# nh-vend_v0_2.net
KiCad netlist of a schematic drawn in EAGLE
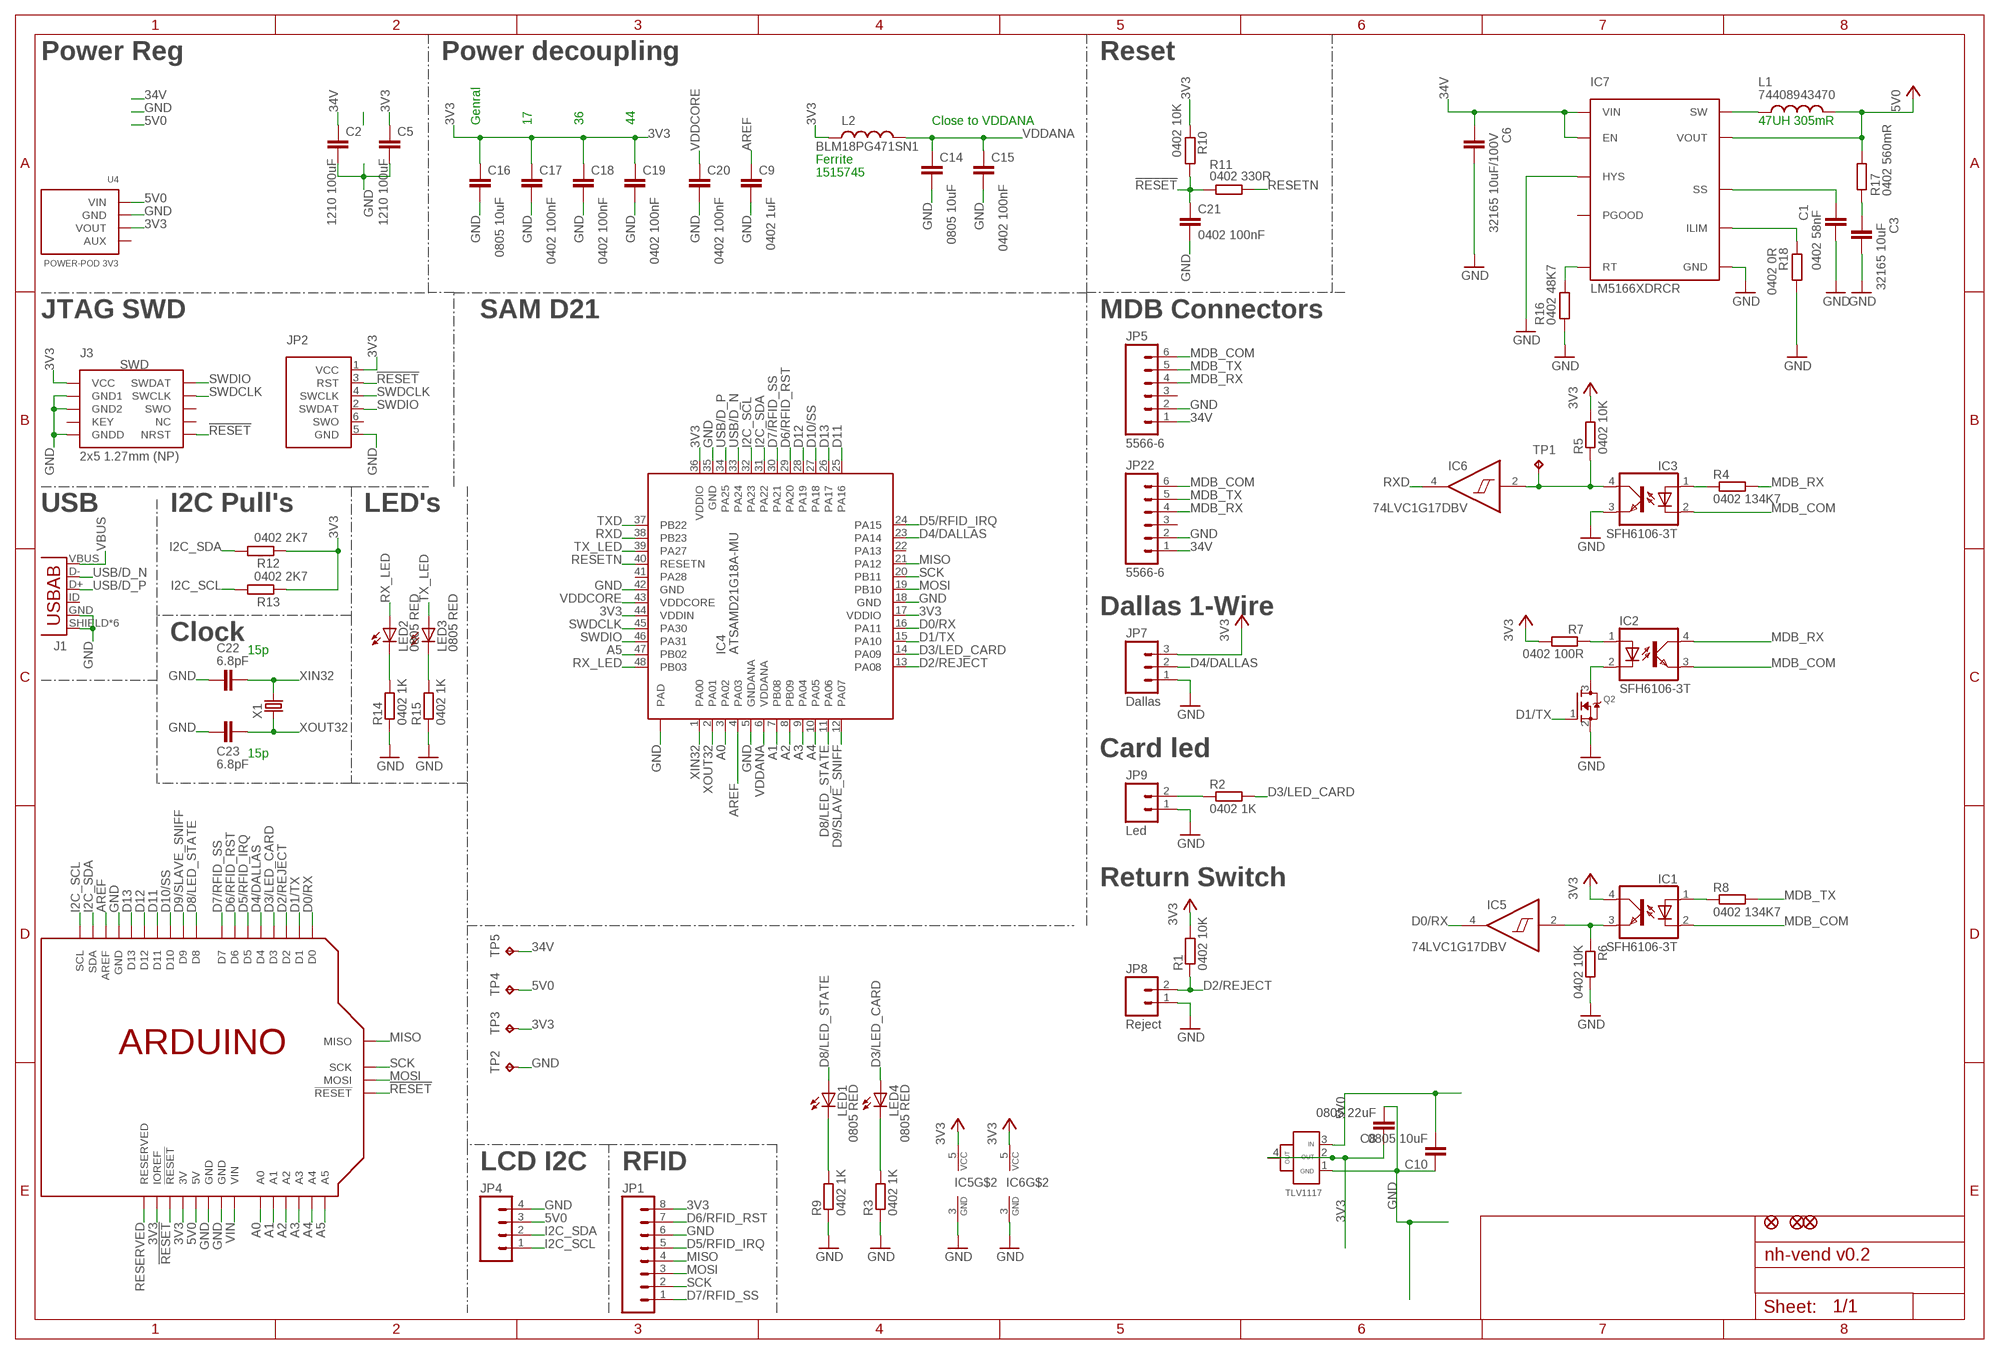
[diagram p0: schematic, sheet 1]

(export (version "E")
  (design (tool "Eeschema 10.0.6"))
  (components
    (comp (ref "C1")
      (value "0402 58nF")
      (footprint "eagle-import:C0402-SMALLER")
      (libsource (lib "eagle-import") (part "C-EUC0402-SMALLER"))
    )
    (comp (ref "C2")
      (value "1210 100uF")
      (footprint "eagle-import:C1210")
      (libsource (lib "eagle-import") (part "C-EUC1210"))
    )
    (comp (ref "C3")
      (value "32165 10uF")
      (footprint "eagle-import:C3216")
      (libsource (lib "eagle-import") (part "C-EUC3216"))
    )
    (comp (ref "C5")
      (value "1210 100uF")
      (footprint "eagle-import:C1210")
      (libsource (lib "eagle-import") (part "C-EUC1210"))
    )
    (comp (ref "C6")
      (value "32165 10uF/100V")
      (footprint "eagle-import:C3216")
      (libsource (lib "eagle-import") (part "C-EUC3216"))
    )
    (comp (ref "C8")
      (value "0805 22uF")
      (footprint "eagle-import:C0805")
      (libsource (lib "eagle-import") (part "rcl_C-EUC0805"))
    )
    (comp (ref "C9")
      (value "0402 1uF")
      (footprint "eagle-import:C0402-SMALLER")
      (libsource (lib "eagle-import") (part "C-EUC0402-SMALLER"))
    )
    (comp (ref "C10")
      (value "0805 10uF")
      (footprint "eagle-import:C0805")
      (libsource (lib "eagle-import") (part "rcl_C-EUC0805"))
    )
    (comp (ref "C14")
      (value "0805 10uF")
      (footprint "eagle-import:C0805K")
      (libsource (lib "eagle-import") (part "C-EUC0805K"))
    )
    (comp (ref "C15")
      (value "0402 100nF")
      (footprint "eagle-import:C0402-SMALLER")
      (libsource (lib "eagle-import") (part "C-EUC0402-SMALLER"))
    )
    (comp (ref "C16")
      (value "0805 10uF")
      (footprint "eagle-import:C0805K")
      (libsource (lib "eagle-import") (part "C-EUC0805K"))
    )
    (comp (ref "C17")
      (value "0402 100nF")
      (footprint "eagle-import:C0402-SMALLER")
      (libsource (lib "eagle-import") (part "C-EUC0402-SMALLER"))
    )
    (comp (ref "C18")
      (value "0402 100nF")
      (footprint "eagle-import:C0402-SMALLER")
      (libsource (lib "eagle-import") (part "C-EUC0402-SMALLER"))
    )
    (comp (ref "C19")
      (value "0402 100nF")
      (footprint "eagle-import:C0402-SMALLER")
      (libsource (lib "eagle-import") (part "C-EUC0402-SMALLER"))
    )
    (comp (ref "C20")
      (value "0402 100nF")
      (footprint "eagle-import:C0402-SMALLER")
      (libsource (lib "eagle-import") (part "C-EUC0402-SMALLER"))
    )
    (comp (ref "C21")
      (value "0402 100nF")
      (footprint "eagle-import:C0402-SMALLER")
      (libsource (lib "eagle-import") (part "C-EUC0402-SMALLER"))
    )
    (comp (ref "C22")
      (value "6.8pF")
      (footprint "eagle-import:C0402-SMALLER")
      (libsource (lib "eagle-import") (part "C-EUC0402-SMALLER"))
    )
    (comp (ref "C23")
      (value "6.8pF")
      (footprint "eagle-import:C0402-SMALLER")
      (libsource (lib "eagle-import") (part "C-EUC0402-SMALLER"))
    )
    (comp (ref "IC1")
      (value "SFH6106-3T")
      (footprint "eagle-import:SO04")
      (libsource (lib "eagle-import") (part "OPTO-DC"))
    )
    (comp (ref "IC2")
      (value "SFH6106-3T")
      (footprint "eagle-import:SO04")
      (libsource (lib "eagle-import") (part "OPTO-DC"))
    )
    (comp (ref "IC3")
      (value "SFH6106-3T")
      (footprint "eagle-import:SO04")
      (libsource (lib "eagle-import") (part "OPTO-DC"))
    )
    (comp (ref "IC4")
      (value "ATSAMD21G18A-MU")
      (footprint "eagle-import:QFN48-LWK")
      (libsource (lib "eagle-import") (part "ATSAMD21G-LWK"))
    )
    (comp (ref "IC5")
      (value "74LVC1G17DBV")
      (footprint "eagle-import:SOT23-5")
      (libsource (lib "eagle-import") (part "741G17DBVLVC"))
    )
    (comp (ref "IC6")
      (value "74LVC1G17DBV")
      (footprint "eagle-import:SOT23-5")
      (libsource (lib "eagle-import") (part "741G17DBVLVC"))
    )
    (comp (ref "IC7")
      (value "LM5166XDRCR")
      (footprint "eagle-import:VSON-10")
      (libsource (lib "eagle-import") (part "LM5166"))
    )
    (comp (ref "J1")
      (value "ZX62-AB-5PA(11)")
      (footprint "eagle-import:USB-AB-MICRO-SMD_LWK")
      (libsource (lib "eagle-import") (part "USB-AB-LWK"))
    )
    (comp (ref "J3")
      (value "2x5 1.27mm (NP)")
      (footprint "eagle-import:PINHEAD_2X05_127")
      (libsource (lib "eagle-import") (part "SWD_SHROUD-PINHEAD"))
    )
    (comp (ref "JP1")
      (value "M081X08")
      (footprint "eagle-import:1X08")
      (libsource (lib "eagle-import") (part "M081X08"))
    )
    (comp (ref "JP2")
      (value "(NP)")
      (footprint "eagle-import:TC2030-MCP-NL")
      (libsource (lib "eagle-import") (part "TC2030-SWDNL"))
    )
    (comp (ref "JP3")
      (value "FIDUCIAL1X2.5-STOP")
      (footprint "eagle-import:FIDUCIAL-1X2.5-STOP")
      (libsource (lib "eagle-import") (part "FIDUCIAL1X2.5-STOP"))
    )
    (comp (ref "JP4")
      (value "M04PTH")
      (footprint "eagle-import:1X04")
      (libsource (lib "eagle-import") (part "M04PTH"))
    )
    (comp (ref "JP5")
      (value "5566-6")
      (footprint "eagle-import:5566-6")
      (fields (field (name "MF") "Molex"))
      (libsource (lib "eagle-import") (part "M06-5566"))
    )
    (comp (ref "JP6")
      (value "FIDUCIAL1X2.5-STOP")
      (footprint "eagle-import:FIDUCIAL-1X2.5-STOP")
      (libsource (lib "eagle-import") (part "FIDUCIAL1X2.5-STOP"))
    )
    (comp (ref "JP7")
      (value "Dallas")
      (footprint "eagle-import:SCREWTERMINAL-5MM-3")
      (libsource (lib "eagle-import") (part "M03-SCREW-5MM"))
    )
    (comp (ref "JP8")
      (value "Reject")
      (footprint "eagle-import:SCREWTERMINAL-5MM-2")
      (libsource (lib "eagle-import") (part "M025MM"))
    )
    (comp (ref "JP9")
      (value "Led")
      (footprint "eagle-import:SCREWTERMINAL-5MM-2")
      (libsource (lib "eagle-import") (part "M025MM"))
    )
    (comp (ref "JP10")
      (value "FIDUCIAL1X2.5-STOP")
      (footprint "eagle-import:FIDUCIAL-1X2.5-STOP")
      (libsource (lib "eagle-import") (part "FIDUCIAL1X2.5-STOP"))
    )
    (comp (ref "JP22")
      (value "5566-6")
      (footprint "eagle-import:5566-6")
      (fields (field (name "MF") "Molex"))
      (libsource (lib "eagle-import") (part "M06-5566"))
    )
    (comp (ref "L1")
      (value "74408943470")
      (footprint "eagle-import:WE-SPC_48XX")
      (libsource (lib "eagle-import") (part "INDUCTOR-WE-SPC"))
    )
    (comp (ref "L2")
      (value "BLM18PG471SN1")
      (footprint "eagle-import:C0603K-SMALL")
      (libsource (lib "eagle-import") (part "INDUCTOR0603K-SMALL"))
    )
    (comp (ref "LED1")
      (value "0805 RED")
      (footprint "eagle-import:LED-0805-1206")
      (libsource (lib "eagle-import") (part "LED0805-1206"))
    )
    (comp (ref "LED2")
      (value "0805 RED")
      (footprint "eagle-import:LED-0805-1206")
      (libsource (lib "eagle-import") (part "LED0805-1206"))
    )
    (comp (ref "LED3")
      (value "0805 RED")
      (footprint "eagle-import:LED-0805-1206")
      (libsource (lib "eagle-import") (part "LED0805-1206"))
    )
    (comp (ref "LED4")
      (value "0805 RED")
      (footprint "eagle-import:LED-0805-1206")
      (libsource (lib "eagle-import") (part "LED0805-1206"))
    )
    (comp (ref "Q2")
      (value "MOSFET-N-SOT23-SPARK")
      (footprint "eagle-import:SOT23-3")
      (libsource (lib "eagle-import") (part "MOSFET-N-SOT23-SPARK"))
    )
    (comp (ref "R1")
      (value "0402 10K")
      (footprint "eagle-import:R0402-SMALLER")
      (libsource (lib "eagle-import") (part "R-EU_R0402-SMALLER"))
    )
    (comp (ref "R2")
      (value "0402 1K")
      (footprint "eagle-import:R0402-SMALLER")
      (libsource (lib "eagle-import") (part "R-EU_R0402-SMALLER"))
    )
    (comp (ref "R3")
      (value "0402 1K")
      (footprint "eagle-import:R0402-SMALLER")
      (libsource (lib "eagle-import") (part "R-EU_R0402-SMALLER"))
    )
    (comp (ref "R4")
      (value "0402 134K7")
      (footprint "eagle-import:R0402-SMALLER")
      (libsource (lib "eagle-import") (part "R-EU_R0402-SMALLER"))
    )
    (comp (ref "R5")
      (value "0402 10K")
      (footprint "eagle-import:R0402-SMALLER")
      (libsource (lib "eagle-import") (part "R-EU_R0402-SMALLER"))
    )
    (comp (ref "R6")
      (value "0402 10K")
      (footprint "eagle-import:R0402-SMALLER")
      (libsource (lib "eagle-import") (part "R-EU_R0402-SMALLER"))
    )
    (comp (ref "R7")
      (value "0402 100R")
      (footprint "eagle-import:R0402-SMALLER")
      (libsource (lib "eagle-import") (part "R-EU_R0402-SMALLER"))
    )
    (comp (ref "R8")
      (value "0402 134K7")
      (footprint "eagle-import:R0402-SMALLER")
      (libsource (lib "eagle-import") (part "R-EU_R0402-SMALLER"))
    )
    (comp (ref "R9")
      (value "0402 1K")
      (footprint "eagle-import:R0402-SMALLER")
      (libsource (lib "eagle-import") (part "R-EU_R0402-SMALLER"))
    )
    (comp (ref "R10")
      (value "0402 10K")
      (footprint "eagle-import:R0402-SMALLER")
      (libsource (lib "eagle-import") (part "R-EU_R0402-SMALLER"))
    )
    (comp (ref "R11")
      (value "0402 330R")
      (footprint "eagle-import:R0402-SMALLER")
      (libsource (lib "eagle-import") (part "R-EU_R0402-SMALLER"))
    )
    (comp (ref "R12")
      (value "0402 2K7")
      (footprint "eagle-import:R0402-SMALLER")
      (libsource (lib "eagle-import") (part "R-EU_R0402-SMALLER"))
    )
    (comp (ref "R13")
      (value "0402 2K7")
      (footprint "eagle-import:R0402-SMALLER")
      (libsource (lib "eagle-import") (part "R-EU_R0402-SMALLER"))
    )
    (comp (ref "R14")
      (value "0402 1K")
      (footprint "eagle-import:R0402-SMALLER")
      (libsource (lib "eagle-import") (part "R-EU_R0402-SMALLER"))
    )
    (comp (ref "R15")
      (value "0402 1K")
      (footprint "eagle-import:R0402-SMALLER")
      (libsource (lib "eagle-import") (part "R-EU_R0402-SMALLER"))
    )
    (comp (ref "R16")
      (value "0402 48K7")
      (footprint "eagle-import:R0402-SMALLER")
      (libsource (lib "eagle-import") (part "R-EU_R0402-SMALLER"))
    )
    (comp (ref "R17")
      (value "0402 560mR")
      (footprint "eagle-import:R0402-SMALLER")
      (libsource (lib "eagle-import") (part "R-EU_R0402-SMALLER"))
    )
    (comp (ref "R18")
      (value "0402 0R")
      (footprint "eagle-import:R0402-SMALLER")
      (libsource (lib "eagle-import") (part "R-EU_R0402-SMALLER"))
    )
    (comp (ref "TP1")
      (value "TPPAD1-10-ROUND")
      (footprint "eagle-import:P1-10-ROUND-CAN")
      (libsource (lib "eagle-import") (part "TPPAD1-10-ROUND"))
    )
    (comp (ref "TP2")
      (value "TPPAD1-10-ROUND")
      (footprint "eagle-import:P1-10-ROUND-CAN")
      (libsource (lib "eagle-import") (part "TPPAD1-10-ROUND"))
    )
    (comp (ref "TP3")
      (value "TPPAD1-10-ROUND")
      (footprint "eagle-import:P1-10-ROUND-CAN")
      (libsource (lib "eagle-import") (part "TPPAD1-10-ROUND"))
    )
    (comp (ref "TP4")
      (value "TPPAD1-10-ROUND")
      (footprint "eagle-import:P1-10-ROUND-CAN")
      (libsource (lib "eagle-import") (part "TPPAD1-10-ROUND"))
    )
    (comp (ref "TP5")
      (value "TPPAD1-10-ROUND")
      (footprint "eagle-import:P1-10-ROUND-CAN")
      (libsource (lib "eagle-import") (part "TPPAD1-10-ROUND"))
    )
    (comp (ref "U1")
      (value "ARDUINOSPI-REFRENCE")
      (footprint "eagle-import:ARDUINOR3-LWKTXT-REF-SPI")
      (libsource (lib "eagle-import") (part "ARDUINOSPI-REFRENCE"))
    )
    (comp (ref "U03")
      (value "1117 3V0")
      (footprint "eagle-import:SOT223")
      (libsource (lib "eagle-import") (part "TLV1117-33CDCY"))
    )
    (comp (ref "U4")
      (value "POWER-POD 3V3")
      (footprint "eagle-import:POWER-POD-LANDING")
      (libsource (lib "eagle-import") (part "POWER-POD"))
    )
    (comp (ref "X1")
      (value "RESONATOR_EPSON_FC_145")
      (footprint "eagle-import:RESONATOR_EPSON_FC_145")
      (libsource (lib "eagle-import") (part "RESONATOR_EPSON_FC_145"))
    )
  )
  (nets
    (net (code "1") (name "/34V") (class "Default")
      (node (ref "C2") (pin "1") (pinfunction "1_1") (pintype "passive"))
      (node (ref "C6") (pin "1") (pinfunction "1_1") (pintype "passive"))
      (node (ref "IC7") (pin "2") (pinfunction "VIN_2") (pintype "bidirectional"))
      (node (ref "IC7") (pin "7") (pinfunction "EN_7") (pintype "bidirectional"))
      (node (ref "JP22") (pin "1") (pinfunction "1_1") (pintype "passive"))
      (node (ref "JP5") (pin "1") (pinfunction "1_1") (pintype "passive"))
      (node (ref "TP5") (pin "TP") (pinfunction "TP_TP") (pintype "input"))
    )
    (net (code "2") (name "/A0") (class "Default")
      (node (ref "IC4") (pin "3") (pinfunction "PA02_3") (pintype "bidirectional"))
      (node (ref "U1") (pin "A0") (pinfunction "A0_A0") (pintype "bidirectional"))
    )
    (net (code "3") (name "/A1") (class "Default")
      (node (ref "IC4") (pin "7") (pinfunction "PB08_7") (pintype "bidirectional"))
      (node (ref "U1") (pin "A1") (pinfunction "A1_A1") (pintype "bidirectional"))
    )
    (net (code "4") (name "/A2") (class "Default")
      (node (ref "IC4") (pin "8") (pinfunction "PB09_8") (pintype "bidirectional"))
      (node (ref "U1") (pin "A2") (pinfunction "A2_A2") (pintype "bidirectional"))
    )
    (net (code "5") (name "/A3") (class "Default")
      (node (ref "IC4") (pin "9") (pinfunction "PA04_9") (pintype "bidirectional"))
      (node (ref "U1") (pin "A3") (pinfunction "A3_A3") (pintype "bidirectional"))
    )
    (net (code "6") (name "/A4") (class "Default")
      (node (ref "IC4") (pin "10") (pinfunction "PA05_10") (pintype "bidirectional"))
      (node (ref "U1") (pin "A4") (pinfunction "A4_A4") (pintype "bidirectional"))
    )
    (net (code "7") (name "/A5") (class "Default")
      (node (ref "IC4") (pin "47") (pinfunction "PB02_47") (pintype "bidirectional"))
      (node (ref "U1") (pin "A5") (pinfunction "A5_A5") (pintype "bidirectional"))
    )
    (net (code "8") (name "/AREF") (class "Default")
      (node (ref "C9") (pin "1") (pinfunction "1_1") (pintype "passive"))
      (node (ref "IC4") (pin "4") (pinfunction "PA03_4") (pintype "bidirectional"))
      (node (ref "U1") (pin "AREF") (pinfunction "AREF_AREF") (pintype "bidirectional"))
    )
    (net (code "9") (name "/D0{slash}RX") (class "Default")
      (node (ref "IC4") (pin "16") (pinfunction "PA11_16") (pintype "bidirectional"))
      (node (ref "IC5") (pin "4") (pinfunction "O_4") (pintype "output"))
      (node (ref "U1") (pin "D0") (pinfunction "D0_D0") (pintype "bidirectional"))
    )
    (net (code "10") (name "/D1{slash}TX") (class "Default")
      (node (ref "IC4") (pin "15") (pinfunction "PA10_15") (pintype "bidirectional"))
      (node (ref "Q2") (pin "1") (pinfunction "G_1") (pintype "bidirectional"))
      (node (ref "U1") (pin "D1") (pinfunction "D1_D1") (pintype "bidirectional"))
    )
    (net (code "11") (name "/D2{slash}REJECT") (class "Default")
      (node (ref "IC4") (pin "13") (pinfunction "PA08_13") (pintype "bidirectional"))
      (node (ref "JP8") (pin "2") (pinfunction "2_2") (pintype "passive"))
      (node (ref "R1") (pin "1") (pinfunction "1_1") (pintype "passive"))
      (node (ref "U1") (pin "D2") (pinfunction "D2_D2") (pintype "bidirectional"))
    )
    (net (code "12") (name "/D3{slash}LED_CARD") (class "Default")
      (node (ref "IC4") (pin "14") (pinfunction "PA09_14") (pintype "bidirectional"))
      (node (ref "LED4") (pin "A") (pinfunction "A_A") (pintype "passive"))
      (node (ref "R2") (pin "2") (pinfunction "2_2") (pintype "passive"))
      (node (ref "U1") (pin "D3") (pinfunction "D3_D3") (pintype "bidirectional"))
    )
    (net (code "13") (name "/D4{slash}DALLAS") (class "Default")
      (node (ref "IC4") (pin "23") (pinfunction "PA14_23") (pintype "bidirectional"))
      (node (ref "JP7") (pin "2") (pinfunction "2_2") (pintype "passive"))
      (node (ref "U1") (pin "D4") (pinfunction "D4_D4") (pintype "bidirectional"))
    )
    (net (code "14") (name "/D5{slash}RFID_IRQ") (class "Default")
      (node (ref "IC4") (pin "24") (pinfunction "PA15_24") (pintype "bidirectional"))
      (node (ref "JP1") (pin "5") (pinfunction "5_5") (pintype "passive"))
      (node (ref "U1") (pin "D5") (pinfunction "D5_D5") (pintype "bidirectional"))
    )
    (net (code "15") (name "/D6{slash}RFID_RST") (class "Default")
      (node (ref "IC4") (pin "29") (pinfunction "PA20_29") (pintype "bidirectional"))
      (node (ref "JP1") (pin "7") (pinfunction "7_7") (pintype "passive"))
      (node (ref "U1") (pin "D6") (pinfunction "D6_D6") (pintype "bidirectional"))
    )
    (net (code "16") (name "/D7{slash}RFID_SS") (class "Default")
      (node (ref "IC4") (pin "30") (pinfunction "PA21_30") (pintype "bidirectional"))
      (node (ref "JP1") (pin "1") (pinfunction "1_1") (pintype "passive"))
      (node (ref "U1") (pin "D7") (pinfunction "D7_D7") (pintype "bidirectional"))
    )
    (net (code "17") (name "/D8{slash}LED_STATE") (class "Default")
      (node (ref "IC4") (pin "11") (pinfunction "PA06_11") (pintype "bidirectional"))
      (node (ref "LED1") (pin "A") (pinfunction "A_A") (pintype "passive"))
      (node (ref "U1") (pin "D8") (pinfunction "D8_D8") (pintype "bidirectional"))
    )
    (net (code "18") (name "/D9{slash}SLAVE_SNIFF") (class "Default")
      (node (ref "IC4") (pin "12") (pinfunction "PA07_12") (pintype "bidirectional"))
      (node (ref "U1") (pin "D9") (pinfunction "D9_D9") (pintype "bidirectional"))
    )
    (net (code "19") (name "/D10{slash}SS") (class "Default")
      (node (ref "IC4") (pin "27") (pinfunction "PA18_27") (pintype "bidirectional"))
      (node (ref "U1") (pin "D10") (pinfunction "D10_D10") (pintype "bidirectional"))
    )
    (net (code "20") (name "/D11") (class "Default")
      (node (ref "IC4") (pin "25") (pinfunction "PA16_25") (pintype "bidirectional"))
      (node (ref "U1") (pin "D11") (pinfunction "D11_D11") (pintype "bidirectional"))
    )
    (net (code "21") (name "/D12") (class "Default")
      (node (ref "IC4") (pin "28") (pinfunction "PA19_28") (pintype "bidirectional"))
      (node (ref "U1") (pin "D12") (pinfunction "D12_D12") (pintype "bidirectional"))
    )
    (net (code "22") (name "/D13") (class "Default")
      (node (ref "IC4") (pin "26") (pinfunction "PA17_26") (pintype "bidirectional"))
      (node (ref "U1") (pin "D13") (pinfunction "D13_D13") (pintype "bidirectional"))
    )
    (net (code "23") (name "/I2C_SCL") (class "Default")
      (node (ref "IC4") (pin "32") (pinfunction "PA23_32") (pintype "bidirectional"))
      (node (ref "JP4") (pin "1") (pinfunction "1_1") (pintype "passive"))
      (node (ref "R13") (pin "2") (pinfunction "2_2") (pintype "passive"))
      (node (ref "U1") (pin "SCL") (pinfunction "SCL_SCL") (pintype "bidirectional"))
    )
    (net (code "24") (name "/I2C_SDA") (class "Default")
      (node (ref "IC4") (pin "31") (pinfunction "PA22_31") (pintype "bidirectional"))
      (node (ref "JP4") (pin "2") (pinfunction "2_2") (pintype "passive"))
      (node (ref "R12") (pin "2") (pinfunction "2_2") (pintype "passive"))
      (node (ref "U1") (pin "SDA") (pinfunction "SDA_SDA") (pintype "bidirectional"))
    )
    (net (code "25") (name "/MDB_COM") (class "Default")
      (node (ref "IC1") (pin "2") (pinfunction "C_2") (pintype "passive"))
      (node (ref "IC2") (pin "3") (pinfunction "EMIT_3") (pintype "passive"))
      (node (ref "IC3") (pin "2") (pinfunction "C_2") (pintype "passive"))
      (node (ref "JP22") (pin "6") (pinfunction "6_6") (pintype "passive"))
      (node (ref "JP5") (pin "6") (pinfunction "6_6") (pintype "passive"))
    )
    (net (code "26") (name "/MDB_RX") (class "Default")
      (node (ref "IC2") (pin "4") (pinfunction "COL_4") (pintype "passive"))
      (node (ref "JP22") (pin "4") (pinfunction "4_4") (pintype "passive"))
      (node (ref "JP5") (pin "4") (pinfunction "4_4") (pintype "passive"))
      (node (ref "R4") (pin "2") (pinfunction "2_2") (pintype "passive"))
    )
    (net (code "27") (name "/MDB_TX") (class "Default")
      (node (ref "JP22") (pin "5") (pinfunction "5_5") (pintype "passive"))
      (node (ref "JP5") (pin "5") (pinfunction "5_5") (pintype "passive"))
      (node (ref "R8") (pin "2") (pinfunction "2_2") (pintype "passive"))
    )
    (net (code "28") (name "/MISO") (class "Default")
      (node (ref "IC4") (pin "21") (pinfunction "PA12_21") (pintype "bidirectional"))
      (node (ref "JP1") (pin "4") (pinfunction "4_4") (pintype "passive"))
      (node (ref "U1") (pin "MISO") (pinfunction "MISO_MISO") (pintype "bidirectional"))
    )
    (net (code "29") (name "/MOSI") (class "Default")
      (node (ref "IC4") (pin "19") (pinfunction "PB10_19") (pintype "bidirectional"))
      (node (ref "JP1") (pin "3") (pinfunction "3_3") (pintype "passive"))
      (node (ref "U1") (pin "MOSI") (pinfunction "MOSI_MOSI") (pintype "bidirectional"))
    )
    (net (code "31") (name "/RESETN") (class "Default")
      (node (ref "IC4") (pin "40") (pinfunction "RESETN_40") (pintype "bidirectional"))
      (node (ref "R11") (pin "2") (pinfunction "2_2") (pintype "passive"))
    )
    (net (code "32") (name "/RXD") (class "Default")
      (node (ref "IC4") (pin "38") (pinfunction "PB23_38") (pintype "bidirectional"))
      (node (ref "IC6") (pin "4") (pinfunction "O_4") (pintype "output"))
    )
    (net (code "33") (name "/RX_LED") (class "Default")
      (node (ref "IC4") (pin "48") (pinfunction "PB03_48") (pintype "bidirectional"))
      (node (ref "LED2") (pin "A") (pinfunction "A_A") (pintype "passive"))
    )
    (net (code "34") (name "/SCK") (class "Default")
      (node (ref "IC4") (pin "20") (pinfunction "PB11_20") (pintype "bidirectional"))
      (node (ref "JP1") (pin "2") (pinfunction "2_2") (pintype "passive"))
      (node (ref "U1") (pin "SCK") (pinfunction "SCK_SCK") (pintype "bidirectional"))
    )
    (net (code "35") (name "/SWDCLK") (class "Default")
      (node (ref "IC4") (pin "45") (pinfunction "PA30_45") (pintype "bidirectional"))
      (node (ref "J3") (pin "4") (pinfunction "SWCLK_4") (pintype "bidirectional"))
      (node (ref "JP2") (pin "4") (pinfunction "SWCLK_4") (pintype "output"))
    )
    (net (code "36") (name "/SWDIO") (class "Default")
      (node (ref "IC4") (pin "46") (pinfunction "PA31_46") (pintype "bidirectional"))
      (node (ref "J3") (pin "2") (pinfunction "SWDAT_2") (pintype "bidirectional"))
      (node (ref "JP2") (pin "2") (pinfunction "SWDAT_2") (pintype "bidirectional"))
    )
    (net (code "37") (name "/TXD") (class "Default")
      (node (ref "IC4") (pin "37") (pinfunction "PB22_37") (pintype "bidirectional"))
    )
    (net (code "38") (name "/TX_LED") (class "Default")
      (node (ref "IC4") (pin "39") (pinfunction "PA27_39") (pintype "bidirectional"))
      (node (ref "LED3") (pin "A") (pinfunction "A_A") (pintype "passive"))
    )
    (net (code "39") (name "/USB{slash}D_N") (class "Default")
      (node (ref "IC4") (pin "33") (pinfunction "PA24_33") (pintype "bidirectional"))
      (node (ref "J1") (pin "D-") (pinfunction "D-_D-") (pintype "bidirectional"))
    )
    (net (code "40") (name "/USB{slash}D_P") (class "Default")
      (node (ref "IC4") (pin "34") (pinfunction "PA25_34") (pintype "bidirectional"))
      (node (ref "J1") (pin "D+") (pinfunction "D+_D+") (pintype "bidirectional"))
    )
    (net (code "41") (name "/VBUS") (class "Default")
      (node (ref "J1") (pin "VBUS") (pinfunction "VBUS_VBUS") (pintype "bidirectional"))
    )
    (net (code "42") (name "/VDDANA") (class "Default")
      (node (ref "C14") (pin "1") (pinfunction "1_1") (pintype "passive"))
      (node (ref "C15") (pin "1") (pinfunction "1_1") (pintype "passive"))
      (node (ref "IC4") (pin "6") (pinfunction "VDDANA_6") (pintype "bidirectional"))
      (node (ref "L2") (pin "2") (pinfunction "2_2") (pintype "passive"))
    )
    (net (code "43") (name "/VDDCORE") (class "Default")
      (node (ref "C20") (pin "1") (pinfunction "1_1") (pintype "passive"))
      (node (ref "IC4") (pin "43") (pinfunction "VDDCORE_43") (pintype "bidirectional"))
    )
    (net (code "44") (name "/VIN") (class "Default")
      (node (ref "U1") (pin "VIN") (pinfunction "VIN_VIN") (pintype "power_in"))
    )
    (net (code "45") (name "/XIN32") (class "Default")
      (node (ref "C22") (pin "1") (pinfunction "1_1") (pintype "passive"))
      (node (ref "IC4") (pin "1") (pinfunction "PA00_1") (pintype "bidirectional"))
      (node (ref "X1") (pin "P$2") (pinfunction "2_P$2") (pintype "bidirectional"))
    )
    (net (code "46") (name "/XOUT32") (class "Default")
      (node (ref "C23") (pin "1") (pinfunction "1_1") (pintype "passive"))
      (node (ref "IC4") (pin "2") (pinfunction "PA01_2") (pintype "bidirectional"))
      (node (ref "X1") (pin "P$1") (pinfunction "1_P$1") (pintype "bidirectional"))
    )
    (net (code "47") (name "/~{RESET}") (class "Default")
      (node (ref "C21") (pin "1") (pinfunction "1_1") (pintype "passive"))
      (node (ref "J3") (pin "10") (pinfunction "NRST_10") (pintype "bidirectional"))
      (node (ref "JP2") (pin "3") (pinfunction "RST_3") (pintype "output"))
      (node (ref "R10") (pin "2") (pinfunction "2_2") (pintype "passive"))
      (node (ref "R11") (pin "1") (pinfunction "1_1") (pintype "passive"))
      (node (ref "U1") (pin "!RESET") (pinfunction "~{RESET}_!RESET") (pintype "bidirectional"))
      (node (ref "U1") (pin "!RESET@ISP") (pinfunction "~{RESET}_!RESET@ISP") (pintype "bidirectional"))
    )
    (net (code "48") (name "3V3") (class "Default")
      (node (ref "C16") (pin "1") (pinfunction "1_1") (pintype "passive"))
      (node (ref "C17") (pin "1") (pinfunction "1_1") (pintype "passive"))
      (node (ref "C18") (pin "1") (pinfunction "1_1") (pintype "passive"))
      (node (ref "C19") (pin "1") (pinfunction "1_1") (pintype "passive"))
      (node (ref "C5") (pin "1") (pinfunction "1_1") (pintype "passive"))
      (node (ref "C8") (pin "1") (pinfunction "1_1") (pintype "passive"))
      (node (ref "IC1") (pin "4") (pinfunction "COL_4") (pintype "passive"))
      (node (ref "IC4") (pin "17") (pinfunction "VDDIO_17") (pintype "bidirectional"))
      (node (ref "IC4") (pin "36") (pinfunction "VDDIO_36") (pintype "bidirectional"))
      (node (ref "IC4") (pin "44") (pinfunction "VDDIN_44") (pintype "bidirectional"))
      (node (ref "IC5") (pin "5") (pinfunction "VCC_5") (pintype "power_in"))
      (node (ref "IC6") (pin "5") (pinfunction "VCC_5") (pintype "power_in"))
      (node (ref "J3") (pin "1") (pinfunction "VCC_1") (pintype "power_in"))
      (node (ref "JP1") (pin "8") (pinfunction "8_8") (pintype "passive"))
      (node (ref "JP2") (pin "1") (pinfunction "VCC_1") (pintype "power_in"))
      (node (ref "JP7") (pin "3") (pinfunction "3_3") (pintype "passive"))
      (node (ref "L2") (pin "1") (pinfunction "1_1") (pintype "passive"))
      (node (ref "R1") (pin "2") (pinfunction "2_2") (pintype "passive"))
      (node (ref "R10") (pin "1") (pinfunction "1_1") (pintype "passive"))
      (node (ref "R12") (pin "1") (pinfunction "1_1") (pintype "passive"))
      (node (ref "R13") (pin "1") (pinfunction "1_1") (pintype "passive"))
      (node (ref "R5") (pin "2") (pinfunction "2_2") (pintype "passive"))
      (node (ref "R7") (pin "2") (pinfunction "2_2") (pintype "passive"))
      (node (ref "TP3") (pin "TP") (pinfunction "TP_TP") (pintype "input"))
      (node (ref "U03") (pin "2") (pinfunction "OUT1_2") (pintype "bidirectional"))
      (node (ref "U03") (pin "4") (pinfunction "OUT2_4") (pintype "bidirectional"))
      (node (ref "U1") (pin "3V") (pinfunction "3V_3V") (pintype "power_in"))
      (node (ref "U1") (pin "IOREF") (pinfunction "IOREF_IOREF") (pintype "output"))
      (node (ref "U4") (pin "3") (pinfunction "VOUT_3") (pintype "bidirectional"))
    )
    (net (code "49") (name "5V0") (class "Default")
      (node (ref "C10") (pin "2") (pinfunction "2_2") (pintype "passive"))
      (node (ref "IC7") (pin "8") (pinfunction "VOUT_8") (pintype "bidirectional"))
      (node (ref "JP4") (pin "3") (pinfunction "3_3") (pintype "passive"))
      (node (ref "L1") (pin "2") (pinfunction "2_2") (pintype "passive"))
      (node (ref "R17") (pin "1") (pinfunction "1_1") (pintype "passive"))
      (node (ref "TP4") (pin "TP") (pinfunction "TP_TP") (pintype "input"))
      (node (ref "U03") (pin "3") (pinfunction "IN_3") (pintype "bidirectional"))
      (node (ref "U1") (pin "5V") (pinfunction "5V_5V") (pintype "power_in"))
      (node (ref "U1") (pin "5V@ISP") (pinfunction "5V_5V@ISP") (pintype "power_in"))
      (node (ref "U4") (pin "1") (pinfunction "VIN_1") (pintype "bidirectional"))
    )
    (net (code "50") (name "GND") (class "Default")
      (node (ref "C1") (pin "2") (pinfunction "2_2") (pintype "passive"))
      (node (ref "C10") (pin "1") (pinfunction "1_1") (pintype "passive"))
      (node (ref "C14") (pin "2") (pinfunction "2_2") (pintype "passive"))
      (node (ref "C15") (pin "2") (pinfunction "2_2") (pintype "passive"))
      (node (ref "C16") (pin "2") (pinfunction "2_2") (pintype "passive"))
      (node (ref "C17") (pin "2") (pinfunction "2_2") (pintype "passive"))
      (node (ref "C18") (pin "2") (pinfunction "2_2") (pintype "passive"))
      (node (ref "C19") (pin "2") (pinfunction "2_2") (pintype "passive"))
      (node (ref "C2") (pin "2") (pinfunction "2_2") (pintype "passive"))
      (node (ref "C20") (pin "2") (pinfunction "2_2") (pintype "passive"))
      (node (ref "C21") (pin "2") (pinfunction "2_2") (pintype "passive"))
      (node (ref "C22") (pin "2") (pinfunction "2_2") (pintype "passive"))
      (node (ref "C23") (pin "2") (pinfunction "2_2") (pintype "passive"))
      (node (ref "C3") (pin "2") (pinfunction "2_2") (pintype "passive"))
      (node (ref "C5") (pin "2") (pinfunction "2_2") (pintype "passive"))
      (node (ref "C6") (pin "2") (pinfunction "2_2") (pintype "passive"))
      (node (ref "C8") (pin "2") (pinfunction "2_2") (pintype "passive"))
      (node (ref "C9") (pin "2") (pinfunction "2_2") (pintype "passive"))
      (node (ref "IC3") (pin "3") (pinfunction "EMIT_3") (pintype "passive"))
      (node (ref "IC4") (pin "18") (pinfunction "GND_18") (pintype "bidirectional"))
      (node (ref "IC4") (pin "35") (pinfunction "GND_35") (pintype "bidirectional"))
      (node (ref "IC4") (pin "42") (pinfunction "GND_42") (pintype "bidirectional"))
      (node (ref "IC4") (pin "5") (pinfunction "GNDANA_5") (pintype "bidirectional"))
      (node (ref "IC4") (pin "EXP") (pinfunction "PAD_EXP") (pintype "bidirectional"))
      (node (ref "IC5") (pin "3") (pinfunction "GND_3") (pintype "power_in"))
      (node (ref "IC6") (pin "3") (pinfunction "GND_3") (pintype "power_in"))
      (node (ref "IC7") (pin "10") (pinfunction "GND_10") (pintype "bidirectional"))
      (node (ref "IC7") (pin "9") (pinfunction "HYS_9") (pintype "bidirectional"))
      (node (ref "IC7") (pin "PAD") (pinfunction "GND_PAD") (pintype "bidirectional"))
      (node (ref "J1") (pin "GND") (pinfunction "GND_GND") (pintype "bidirectional"))
      (node (ref "J1") (pin "SHIELD") (pinfunction "SHIELD_SHIELD") (pintype "bidirectional"))
      (node (ref "J1") (pin "SHIELD@0") (pinfunction "SHIELD_SHIELD@0") (pintype "bidirectional"))
      (node (ref "J1") (pin "SHIELD@1") (pinfunction "SHIELD_SHIELD@1") (pintype "bidirectional"))
      (node (ref "J1") (pin "SHIELD@2") (pinfunction "SHIELD_SHIELD@2") (pintype "bidirectional"))
      (node (ref "J1") (pin "SHIELD@3") (pinfunction "SHIELD_SHIELD@3") (pintype "bidirectional"))
      (node (ref "J1") (pin "SHIELD@5") (pinfunction "SHIELD_SHIELD@5") (pintype "bidirectional"))
      (node (ref "J3") (pin "3") (pinfunction "GND1_3") (pintype "power_in"))
      (node (ref "J3") (pin "5") (pinfunction "GND2_5") (pintype "power_in"))
      (node (ref "J3") (pin "9") (pinfunction "GNDD_9") (pintype "power_in"))
      (node (ref "JP1") (pin "6") (pinfunction "6_6") (pintype "passive"))
      (node (ref "JP2") (pin "5") (pinfunction "GND_5") (pintype "power_in"))
      (node (ref "JP22") (pin "2") (pinfunction "2_2") (pintype "passive"))
      (node (ref "JP4") (pin "4") (pinfunction "4_4") (pintype "passive"))
      (node (ref "JP5") (pin "2") (pinfunction "2_2") (pintype "passive"))
      (node (ref "JP7") (pin "1") (pinfunction "1_1") (pintype "passive"))
      (node (ref "JP8") (pin "1") (pinfunction "1_1") (pintype "passive"))
      (node (ref "JP9") (pin "1") (pinfunction "1_1") (pintype "passive"))
      (node (ref "Q2") (pin "2") (pinfunction "S_2") (pintype "bidirectional"))
      (node (ref "R14") (pin "1") (pinfunction "1_1") (pintype "passive"))
      (node (ref "R15") (pin "1") (pinfunction "1_1") (pintype "passive"))
      (node (ref "R16") (pin "1") (pinfunction "1_1") (pintype "passive"))
      (node (ref "R18") (pin "1") (pinfunction "1_1") (pintype "passive"))
      (node (ref "R3") (pin "1") (pinfunction "1_1") (pintype "passive"))
      (node (ref "R6") (pin "2") (pinfunction "2_2") (pintype "passive"))
      (node (ref "R9") (pin "1") (pinfunction "1_1") (pintype "passive"))
      (node (ref "TP2") (pin "TP") (pinfunction "TP_TP") (pintype "input"))
      (node (ref "U03") (pin "1") (pinfunction "GND_1") (pintype "bidirectional"))
      (node (ref "U1") (pin "GND@1") (pinfunction "GND_GND@1") (pintype "power_in"))
      (node (ref "U1") (pin "GND@2") (pinfunction "GND_GND@2") (pintype "power_in"))
      (node (ref "U1") (pin "GND@3") (pinfunction "GND_GND@3") (pintype "power_in"))
      (node (ref "U1") (pin "GND@ISP") (pinfunction "GND_GND@ISP") (pintype "power_in"))
      (node (ref "U4") (pin "2") (pinfunction "GND_2") (pintype "bidirectional"))
    )
    (net (code "51") (name "Net-(C3-Pad1)") (class "Default")
      (node (ref "C3") (pin "1") (pinfunction "1_1") (pintype "passive"))
      (node (ref "R17") (pin "2") (pinfunction "2_2") (pintype "passive"))
    )
    (net (code "52") (name "Net-(IC1-A)") (class "Default")
      (node (ref "IC1") (pin "1") (pinfunction "A_1") (pintype "passive"))
      (node (ref "R8") (pin "1") (pinfunction "1_1") (pintype "passive"))
    )
    (net (code "53") (name "Net-(IC1-EMIT)") (class "Default")
      (node (ref "IC1") (pin "3") (pinfunction "EMIT_3") (pintype "passive"))
      (node (ref "IC5") (pin "2") (pinfunction "I_2") (pintype "input"))
      (node (ref "R6") (pin "1") (pinfunction "1_1") (pintype "passive"))
    )
    (net (code "54") (name "Net-(IC2-A)") (class "Default")
      (node (ref "IC2") (pin "1") (pinfunction "A_1") (pintype "passive"))
      (node (ref "R7") (pin "1") (pinfunction "1_1") (pintype "passive"))
    )
    (net (code "55") (name "Net-(IC2-C)") (class "Default")
      (node (ref "IC2") (pin "2") (pinfunction "C_2") (pintype "passive"))
      (node (ref "Q2") (pin "3") (pinfunction "D_3") (pintype "bidirectional"))
    )
    (net (code "56") (name "Net-(IC3-A)") (class "Default")
      (node (ref "IC3") (pin "1") (pinfunction "A_1") (pintype "passive"))
      (node (ref "R4") (pin "1") (pinfunction "1_1") (pintype "passive"))
    )
    (net (code "57") (name "Net-(IC3-COL)") (class "Default")
      (node (ref "IC3") (pin "4") (pinfunction "COL_4") (pintype "passive"))
      (node (ref "IC6") (pin "2") (pinfunction "I_2") (pintype "input"))
      (node (ref "R5") (pin "1") (pinfunction "1_1") (pintype "passive"))
      (node (ref "TP1") (pin "TP") (pinfunction "TP_TP") (pintype "input"))
    )
    (net (code "58") (name "Net-(IC7-ILIM)") (class "Default")
      (node (ref "IC7") (pin "3") (pinfunction "ILIM_3") (pintype "bidirectional"))
      (node (ref "R18") (pin "2") (pinfunction "2_2") (pintype "passive"))
    )
    (net (code "59") (name "Net-(IC7-RT)") (class "Default")
      (node (ref "IC7") (pin "5") (pinfunction "RT_5") (pintype "bidirectional"))
      (node (ref "R16") (pin "2") (pinfunction "2_2") (pintype "passive"))
    )
    (net (code "60") (name "Net-(IC7-SS)") (class "Default")
      (node (ref "C1") (pin "1") (pinfunction "1_1") (pintype "passive"))
      (node (ref "IC7") (pin "4") (pinfunction "SS_4") (pintype "bidirectional"))
    )
    (net (code "61") (name "Net-(IC7-SW)") (class "Default")
      (node (ref "IC7") (pin "1") (pinfunction "SW_1") (pintype "bidirectional"))
      (node (ref "L1") (pin "1") (pinfunction "1_1") (pintype "passive"))
    )
    (net (code "62") (name "Net-(JP9-Pad2)") (class "Default")
      (node (ref "JP9") (pin "2") (pinfunction "2_2") (pintype "passive"))
      (node (ref "R2") (pin "1") (pinfunction "1_1") (pintype "passive"))
    )
    (net (code "63") (name "Net-(LED1-PadC)") (class "Default")
      (node (ref "LED1") (pin "C") (pinfunction "C_C") (pintype "passive"))
      (node (ref "R9") (pin "2") (pinfunction "2_2") (pintype "passive"))
    )
    (net (code "64") (name "Net-(LED2-PadC)") (class "Default")
      (node (ref "LED2") (pin "C") (pinfunction "C_C") (pintype "passive"))
      (node (ref "R14") (pin "2") (pinfunction "2_2") (pintype "passive"))
    )
    (net (code "65") (name "Net-(LED3-PadC)") (class "Default")
      (node (ref "LED3") (pin "C") (pinfunction "C_C") (pintype "passive"))
      (node (ref "R15") (pin "2") (pinfunction "2_2") (pintype "passive"))
    )
    (net (code "66") (name "Net-(LED4-PadC)") (class "Default")
      (node (ref "LED4") (pin "C") (pinfunction "C_C") (pintype "passive"))
      (node (ref "R3") (pin "2") (pinfunction "2_2") (pintype "passive"))
    )
    (net (code "67") (name "unconnected-(IC4-PA13-Pad22)") (class "Default")
      (node (ref "IC4") (pin "22") (pinfunction "PA13_22") (pintype "bidirectional"))
    )
    (net (code "68") (name "unconnected-(IC4-PA28-Pad41)") (class "Default")
      (node (ref "IC4") (pin "41") (pinfunction "PA28_41") (pintype "bidirectional"))
    )
    (net (code "69") (name "unconnected-(IC7-PGOOD-Pad6)") (class "Default")
      (node (ref "IC7") (pin "6") (pinfunction "PGOOD_6") (pintype "bidirectional"))
    )
    (net (code "70") (name "unconnected-(J1-USBID-PadID)") (class "Default")
      (node (ref "J1") (pin "ID") (pinfunction "USBID_ID") (pintype "bidirectional"))
    )
    (net (code "71") (name "unconnected-(J3-KEY-Pad7)") (class "Default")
      (node (ref "J3") (pin "7") (pinfunction "KEY_7") (pintype "bidirectional"))
    )
    (net (code "72") (name "unconnected-(J3-NC-Pad8)") (class "Default")
      (node (ref "J3") (pin "8") (pinfunction "NC_8") (pintype "no_connect"))
    )
    (net (code "73") (name "unconnected-(J3-SWO-Pad6)") (class "Default")
      (node (ref "J3") (pin "6") (pinfunction "SWO_6") (pintype "bidirectional"))
    )
    (net (code "74") (name "unconnected-(JP2-SWO-Pad6)") (class "Default")
      (node (ref "JP2") (pin "6") (pinfunction "SWO_6") (pintype "input"))
    )
    (net (code "75") (name "unconnected-(JP5-Pad3)") (class "Default")
      (node (ref "JP5") (pin "3") (pinfunction "3_3") (pintype "passive"))
    )
    (net (code "76") (name "unconnected-(JP22-Pad3)") (class "Default")
      (node (ref "JP22") (pin "3") (pinfunction "3_3") (pintype "passive"))
    )
    (net (code "77") (name "unconnected-(U1-PadRESERVED)") (class "Default")
      (node (ref "U1") (pin "RESERVED") (pinfunction "RESERVED_RESERVED") (pintype "no_connect"))
    )
    (net (code "78") (name "unconnected-(U4-AUX-Pad4)") (class "Default")
      (node (ref "U4") (pin "4") (pinfunction "AUX_4") (pintype "bidirectional"))
    )
  )
)
